# MCU_ESP32_S3.net
KiCad netlist of a schematic drawn in Altium Designer
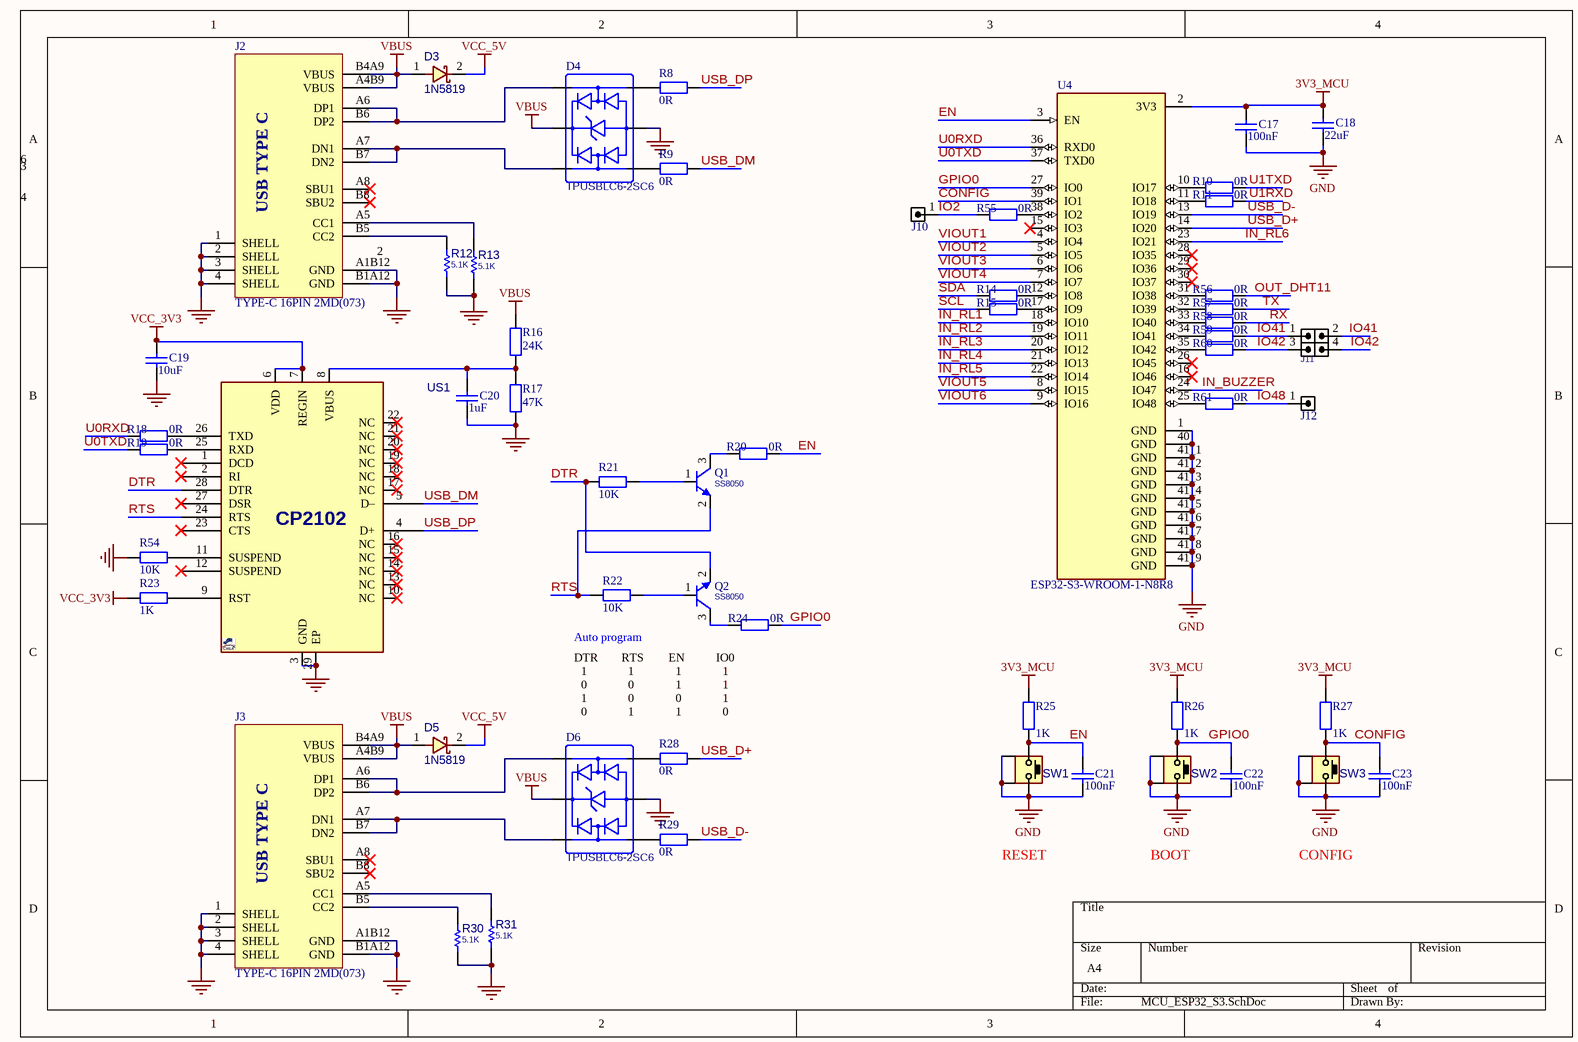
[diagram p0: MCU_ESP32_S3.SchDoc]

(export (version "E")
  (design (tool "Eeschema 10.0.6"))
  (components
    (comp (ref "C17")
      (value "100nF_0603_1%")
      (footprint "tu 0603")
      (description "Capacitor, Ceramic, 50V")
      (fields (field (name "MA_HANG") "100nF"))
      (libsource (lib "THU VIEN SCH") (part "Tu 0603 470pF 50V 10%"))
    )
    (comp (ref "C18")
      (value "22uF_0603_1%")
      (footprint "tu 0603")
      (description "Capacitor, Ceramic, 50V")
      (fields (field (name "MA_HANG") "22uF"))
      (libsource (lib "THU VIEN SCH") (part "Tu 0603 470pF 50V 10%"))
    )
    (comp (ref "C19")
      (value "10uF_0603_1%")
      (footprint "tu 0603")
      (description "Capacitor, Ceramic, 50V")
      (fields (field (name "MA_HANG") "10uF"))
      (libsource (lib "THU VIEN SCH") (part "Tu 0603 470pF 50V 10%"))
    )
    (comp (ref "C20")
      (value "1uF_0603_1%")
      (footprint "tu 0603")
      (description "Capacitor, Ceramic, 50V")
      (fields (field (name "MA_HANG") "1uF"))
      (libsource (lib "THU VIEN SCH") (part "Tu 0603 470pF 50V 10%"))
    )
    (comp (ref "C21")
      (value "100nF_0603_1%")
      (footprint "tu 0603")
      (description "Capacitor, Ceramic, 50V")
      (fields (field (name "MA_HANG") "100nF"))
      (libsource (lib "THU VIEN SCH") (part "Tu 0603 470pF 50V 10%"))
    )
    (comp (ref "C22")
      (value "100nF_0603_1%")
      (footprint "tu 0603")
      (description "Capacitor, Ceramic, 50V")
      (fields (field (name "MA_HANG") "100nF"))
      (libsource (lib "THU VIEN SCH") (part "Tu 0603 470pF 50V 10%"))
    )
    (comp (ref "C23")
      (value "100nF_0603_1%")
      (footprint "tu 0603")
      (description "Capacitor, Ceramic, 50V")
      (fields (field (name "MA_HANG") "100nF"))
      (libsource (lib "THU VIEN SCH") (part "Tu 0603 470pF 50V 10%"))
    )
    (comp (ref "D3")
      (value "1N5819")
      (footprint "D_SOD123W")
      (description "DIODE, SCHOTTKY, 40V, 1A")
      (fields (field (name "MANF") "DIODES") (field (name "MANF_P#") "1N5819HW-7-F"))
      (libsource (lib "AH_Library") (part "DIODE_SMD_SCHOTTKY_1N5819"))
    )
    (comp (ref "D4")
      (value "TPUSBLC6-2SC6")
      (footprint "SOT-23-6_L2.9-W1.6-P0.95-LS2.8-BR")
      (description "ESD ROHS SOT23-6 DIODES")
      (fields (field (name "LCSC PART NUMBER") "C558442") (field (name "MANUFACTURER") "TECH PUBLIC"))
      (libsource (lib "ESP32 S3 Gateway") (part "ESD_TPUSBLC6-2SC6"))
    )
    (comp (ref "D5")
      (value "1N5819")
      (footprint "D_SOD123W")
      (description "DIODE, SCHOTTKY, 40V, 1A")
      (fields (field (name "MANF") "DIODES") (field (name "MANF_P#") "1N5819HW-7-F"))
      (libsource (lib "AH_Library") (part "DIODE_SMD_SCHOTTKY_1N5819"))
    )
    (comp (ref "D6")
      (value "TPUSBLC6-2SC6")
      (footprint "SOT-23-6_L2.9-W1.6-P0.95-LS2.8-BR")
      (description "ESD ROHS SOT23-6 DIODES")
      (fields (field (name "LCSC PART NUMBER") "C558442") (field (name "MANUFACTURER") "TECH PUBLIC"))
      (libsource (lib "ESP32 S3 Gateway") (part "ESD_TPUSBLC6-2SC6"))
    )
    (comp (ref "J2")
      (value "TYPE-C 16PIN 2MD(073)")
      (footprint "USB-C-SMD_TYPE-C16PIN")
      (description "5A 1 Surface Mount 16 Female -25℃~+85℃ Type-C SMD USB Connectors ROHS")
      (fields
        (field (name "MANUFACTURER") "SHOU HAN")
        (field (name "MANUFACTURER PART NUMBER") "TYPE-C16PIN")
      )
      (libsource (lib "ESP32 S3 Gateway") (part "TYPE-C 16PIN 2MD(073)"))
    )
    (comp (ref "J3")
      (value "TYPE-C 16PIN 2MD(073)")
      (footprint "USB-C-SMD_TYPE-C16PIN")
      (description "5A 1 Surface Mount 16 Female -25℃~+85℃ Type-C SMD USB Connectors ROHS")
      (fields
        (field (name "MANUFACTURER") "SHOU HAN")
        (field (name "MANUFACTURER PART NUMBER") "TYPE-C16PIN")
      )
      (libsource (lib "ESP32 S3 Gateway") (part "TYPE-C 16PIN 2MD(073)"))
    )
    (comp (ref "J10")
      (value "HDRM1")
      (footprint "HDR_M_1")
      (description "CONN, HEADER, Male, pitch: 2.54mm, 1POS")
      (libsource (lib "AH_Library") (part "HDR_M_1"))
    )
    (comp (ref "J11")
      (value "HDR2M_2X2")
      (footprint "HDR2_M_2X2")
      (description "CONN, HEADER, Male, pitch: 2mm, 4POS")
      (fields (field (name "MANF_P#") "MANF_PART#") (field (name "MANF") "MANF"))
      (libsource (lib "AH_Library") (part "HDR2_M_2X2"))
    )
    (comp (ref "J12")
      (value "HDRM1")
      (footprint "HDR_M_1")
      (description "CONN, HEADER, Male, pitch: 2.54mm, 1POS")
      (libsource (lib "") (part "HDR_M_1_1"))
    )
    (comp (ref "Q1")
      (value "SS8050")
      (footprint "SOT23_3")
      (description "BJT, NPN, 25v, 1.5A, SMD, SOT23")
      (fields (field (name "MANF_P#") "MMBT8050") (field (name "MANF") "GALAXY"))
      (libsource (lib "AH_Library") (part "NPN_MMBT8050_SOT23"))
    )
    (comp (ref "Q2")
      (value "SS8050")
      (footprint "SOT23_3")
      (description "BJT, NPN, 25v, 1.5A, SMD, SOT23")
      (fields (field (name "MANF_P#") "MMBT8050") (field (name "MANF") "GALAXY"))
      (libsource (lib "AH_Library") (part "NPN_MMBT8050_SOT23"))
    )
    (comp (ref "R8")
      (value "0R_0603_1%")
      (footprint "tro smd 0603")
      (description "RES SMD 0603")
      (fields (field (name "MA_HANG") "0R"))
      (libsource (lib "THU VIEN SCH") (part "Tro 0603 5% 10k"))
    )
    (comp (ref "R9")
      (value "0R_0603_1%")
      (footprint "tro smd 0603")
      (description "RES SMD 0603")
      (fields (field (name "MA_HANG") "0R"))
      (libsource (lib "THU VIEN SCH") (part "Tro 0603 5% 10k"))
    )
    (comp (ref "R10")
      (value "0R_0603_1%")
      (footprint "tro smd 0603")
      (description "RES SMD 0603")
      (fields (field (name "MA_HANG") "0R"))
      (libsource (lib "THU VIEN SCH") (part "Tro 0603 5% 10k"))
    )
    (comp (ref "R11")
      (value "0R_0603_1%")
      (footprint "tro smd 0603")
      (description "RES SMD 0603")
      (fields (field (name "MA_HANG") "0R"))
      (libsource (lib "THU VIEN SCH") (part "Tro 0603 5% 10k"))
    )
    (comp (ref "R12")
      (value "5.1K")
      (footprint "R0603")
      (description "RESISTOR, SMD")
      (fields (field (name "Comment") "5K1_0603_1%"))
      (libsource (lib "AH_Library") (part "RES_SMD_0603"))
    )
    (comp (ref "R13")
      (value "5.1K")
      (footprint "R0603")
      (description "RESISTOR, SMD")
      (fields (field (name "Comment") "5K1_0603_1%"))
      (libsource (lib "AH_Library") (part "RES_SMD_0603"))
    )
    (comp (ref "R14")
      (value "0R_0603_1%")
      (footprint "tro smd 0603")
      (description "RES SMD 0603")
      (fields (field (name "MA_HANG") "0R"))
      (libsource (lib "THU VIEN SCH") (part "Tro 0603 5% 10k"))
    )
    (comp (ref "R15")
      (value "0R_0603_1%")
      (footprint "tro smd 0603")
      (description "RES SMD 0603")
      (fields (field (name "MA_HANG") "0R"))
      (libsource (lib "THU VIEN SCH") (part "Tro 0603 5% 10k"))
    )
    (comp (ref "R16")
      (value "24K_0603_1%")
      (footprint "tro smd 0603")
      (description "RES SMD 0603")
      (fields (field (name "MA_HANG") "24K"))
      (libsource (lib "THU VIEN SCH") (part "Tro 0603 5% 10k"))
    )
    (comp (ref "R17")
      (value "47K_0603_1%")
      (footprint "tro smd 0603")
      (description "RES SMD 0603")
      (fields (field (name "MA_HANG") "47K"))
      (libsource (lib "THU VIEN SCH") (part "Tro 0603 5% 10k"))
    )
    (comp (ref "R18")
      (value "0R_0603_1%")
      (footprint "tro smd 0603")
      (description "RES SMD 0603")
      (fields (field (name "MA_HANG") "0R"))
      (libsource (lib "THU VIEN SCH") (part "Tro 0603 5% 10k"))
    )
    (comp (ref "R19")
      (value "0R_0603_1%")
      (footprint "tro smd 0603")
      (description "RES SMD 0603")
      (fields (field (name "MA_HANG") "0R"))
      (libsource (lib "THU VIEN SCH") (part "Tro 0603 5% 10k"))
    )
    (comp (ref "R20")
      (value "0R_0603_1%")
      (footprint "tro smd 0603")
      (description "RES SMD 0603")
      (fields (field (name "MA_HANG") "0R"))
      (libsource (lib "THU VIEN SCH") (part "Tro 0603 5% 10k"))
    )
    (comp (ref "R21")
      (value "10K_0603_1%")
      (footprint "tro smd 0603")
      (description "RES SMD 0603")
      (fields (field (name "MA_HANG") "10K"))
      (libsource (lib "THU VIEN SCH") (part "Tro 0603 5% 10k"))
    )
    (comp (ref "R22")
      (value "10K_0603_1%")
      (footprint "tro smd 0603")
      (description "RES SMD 0603")
      (fields (field (name "MA_HANG") "10K"))
      (libsource (lib "THU VIEN SCH") (part "Tro 0603 5% 10k"))
    )
    (comp (ref "R23")
      (value "1K_0603_1%")
      (footprint "tro smd 0603")
      (description "RES SMD 0603")
      (fields (field (name "MA_HANG") "1K"))
      (libsource (lib "THU VIEN SCH") (part "Tro 0603 5% 10k"))
    )
    (comp (ref "R24")
      (value "0R_0603_1%")
      (footprint "tro smd 0603")
      (description "RES SMD 0603")
      (fields (field (name "MA_HANG") "0R"))
      (libsource (lib "THU VIEN SCH") (part "Tro 0603 5% 10k"))
    )
    (comp (ref "R25")
      (value "1K_0603_1%")
      (footprint "tro smd 0603")
      (description "RES SMD 0603")
      (fields (field (name "MA_HANG") "1K"))
      (libsource (lib "THU VIEN SCH") (part "Tro 0603 5% 10k"))
    )
    (comp (ref "R26")
      (value "1K_0603_1%")
      (footprint "tro smd 0603")
      (description "RES SMD 0603")
      (fields (field (name "MA_HANG") "1K"))
      (libsource (lib "THU VIEN SCH") (part "Tro 0603 5% 10k"))
    )
    (comp (ref "R27")
      (value "1K_0603_1%")
      (footprint "tro smd 0603")
      (description "RES SMD 0603")
      (fields (field (name "MA_HANG") "1K"))
      (libsource (lib "THU VIEN SCH") (part "Tro 0603 5% 10k"))
    )
    (comp (ref "R28")
      (value "0R_0603_1%")
      (footprint "tro smd 0603")
      (description "RES SMD 0603")
      (fields (field (name "MA_HANG") "0R"))
      (libsource (lib "THU VIEN SCH") (part "Tro 0603 5% 10k"))
    )
    (comp (ref "R29")
      (value "0R_0603_1%")
      (footprint "tro smd 0603")
      (description "RES SMD 0603")
      (fields (field (name "MA_HANG") "0R"))
      (libsource (lib "THU VIEN SCH") (part "Tro 0603 5% 10k"))
    )
    (comp (ref "R30")
      (value "5.1K")
      (footprint "R0603")
      (description "RESISTOR, SMD")
      (fields (field (name "Comment") "5K1_0603_1%"))
      (libsource (lib "AH_Library") (part "RES_SMD_0603"))
    )
    (comp (ref "R31")
      (value "5.1K")
      (footprint "R0603")
      (description "RESISTOR, SMD")
      (fields (field (name "Comment") "5K1_0603_1%"))
      (libsource (lib "AH_Library") (part "RES_SMD_0603"))
    )
    (comp (ref "R54")
      (value "10K_0603_1%")
      (footprint "tro smd 0603")
      (description "RES SMD 0603")
      (fields (field (name "MA_HANG") "10K"))
      (libsource (lib "THU VIEN SCH") (part "Tro 0603 5% 10k"))
    )
    (comp (ref "R55")
      (value "0R_0603_1%")
      (footprint "tro smd 0603")
      (description "RES SMD 0603")
      (fields (field (name "MA_HANG") "0R"))
      (libsource (lib "THU VIEN SCH") (part "Tro 0603 5% 10k"))
    )
    (comp (ref "R56")
      (value "0R_0603_1%")
      (footprint "tro smd 0603")
      (description "RES SMD 0603")
      (fields (field (name "MA_HANG") "0R"))
      (libsource (lib "THU VIEN SCH") (part "Tro 0603 5% 10k"))
    )
    (comp (ref "R57")
      (value "0R_0603_1%")
      (footprint "tro smd 0603")
      (description "RES SMD 0603")
      (fields (field (name "MA_HANG") "0R"))
      (libsource (lib "THU VIEN SCH") (part "Tro 0603 5% 10k"))
    )
    (comp (ref "R58")
      (value "0R_0603_1%")
      (footprint "tro smd 0603")
      (description "RES SMD 0603")
      (fields (field (name "MA_HANG") "0R"))
      (libsource (lib "THU VIEN SCH") (part "Tro 0603 5% 10k"))
    )
    (comp (ref "R59")
      (value "0R_0603_1%")
      (footprint "tro smd 0603")
      (description "RES SMD 0603")
      (fields (field (name "MA_HANG") "0R"))
      (libsource (lib "THU VIEN SCH") (part "Tro 0603 5% 10k"))
    )
    (comp (ref "R60")
      (value "0R_0603_1%")
      (footprint "tro smd 0603")
      (description "RES SMD 0603")
      (fields (field (name "MA_HANG") "0R"))
      (libsource (lib "THU VIEN SCH") (part "Tro 0603 5% 10k"))
    )
    (comp (ref "R61")
      (value "0R_0603_1%")
      (footprint "tro smd 0603")
      (description "RES SMD 0603")
      (fields (field (name "MA_HANG") "0R"))
      (libsource (lib "THU VIEN SCH") (part "Tro 0603 5% 10k"))
    )
    (comp (ref "SW1")
      (value "PUSHBUTTON")
      (footprint "SWPBT_SPST_R_6X6X10")
      (description "SWITCH, PUSH BUTTON, TACTILE, THD, SPST, RIGHT")
      (libsource (lib "AH_Library") (part "SWPBT_SPST_R_6X6X10"))
    )
    (comp (ref "SW2")
      (value "PUSHBUTTON")
      (footprint "SWPBT_SPST_R_6X6X10")
      (description "SWITCH, PUSH BUTTON, TACTILE, THD, SPST, RIGHT")
      (libsource (lib "AH_Library") (part "SWPBT_SPST_R_6X6X10"))
    )
    (comp (ref "SW3")
      (value "PUSHBUTTON")
      (footprint "SWPBT_SPST_R_6X6X10")
      (description "SWITCH, PUSH BUTTON, TACTILE, THD, SPST, RIGHT")
      (libsource (lib "AH_Library") (part "SWPBT_SPST_R_6X6X10"))
    )
    (comp (ref "U4")
      (value "ESP32-S3-WROOM-1-N8R8")
      (footprint "XCVR_ESP32S3WROOM1N8R8")
      (description "Bluetooth, WiFi 802.11b/g/n, Bluetooth v5.0 Transceiver Module 2.4GHz PCB Trace Surface Mount")
      (fields (field (name "MF") "Espressif Systems"))
      (libsource (lib "ESP32-S3-WROOM-1-N8R8") (part "ESP32-S3-WROOM-1-N8R8"))
    )
    (comp (ref "US1")
      (value "CP2102_QFN28")
      (footprint "QFN50_28T")
      (description "USB-UART BRIDGE")
      (fields (field (name "MANF") "SILICON LABS") (field (name "MANF_1") "MANF"))
      (libsource (lib "AH_Library") (part "CP2102_QFN28"))
    )
  )
  (nets
    (net (code "1") (name "/CONFIG") (class "Default")
      (node (ref "C23") (pin "1") (pinfunction "1_1") (pintype "passive"))
      (node (ref "R27") (pin "1") (pinfunction "1_1") (pintype "passive"))
      (node (ref "SW3") (pin "1") (pinfunction "1_1") (pintype "passive"))
      (node (ref "U4") (pin "39") (pinfunction "IO1_39") (pintype "bidirectional"))
    )
    (net (code "2") (name "/DTR") (class "Default")
      (node (ref "Q2") (pin "2") (pinfunction "E_2") (pintype "passive"))
      (node (ref "R21") (pin "2") (pinfunction "2_2") (pintype "passive"))
      (node (ref "US1") (pin "28") (pinfunction "DTR_28") (pintype "passive"))
    )
    (net (code "3") (name "/EN") (class "Default")
      (node (ref "C21") (pin "1") (pinfunction "1_1") (pintype "passive"))
      (node (ref "R20") (pin "2") (pinfunction "2_2") (pintype "passive"))
      (node (ref "R25") (pin "1") (pinfunction "1_1") (pintype "passive"))
      (node (ref "SW1") (pin "1") (pinfunction "1_1") (pintype "passive"))
      (node (ref "U4") (pin "3") (pinfunction "EN_3") (pintype "input"))
    )
    (net (code "4") (name "/GPIO0") (class "Default")
      (node (ref "C22") (pin "1") (pinfunction "1_1") (pintype "passive"))
      (node (ref "R24") (pin "2") (pinfunction "2_2") (pintype "passive"))
      (node (ref "R26") (pin "1") (pinfunction "1_1") (pintype "passive"))
      (node (ref "SW2") (pin "1") (pinfunction "1_1") (pintype "passive"))
      (node (ref "U4") (pin "27") (pinfunction "IO0_27") (pintype "bidirectional"))
    )
    (net (code "5") (name "/IN_BUZZER") (class "Default")
      (node (ref "U4") (pin "24") (pinfunction "IO47_24") (pintype "bidirectional"))
    )
    (net (code "6") (name "/IN_RL1") (class "Default")
      (node (ref "U4") (pin "18") (pinfunction "IO10_18") (pintype "bidirectional"))
    )
    (net (code "7") (name "/IN_RL2") (class "Default")
      (node (ref "U4") (pin "19") (pinfunction "IO11_19") (pintype "bidirectional"))
    )
    (net (code "8") (name "/IN_RL3") (class "Default")
      (node (ref "U4") (pin "20") (pinfunction "IO12_20") (pintype "bidirectional"))
    )
    (net (code "9") (name "/IN_RL4") (class "Default")
      (node (ref "U4") (pin "21") (pinfunction "IO13_21") (pintype "bidirectional"))
    )
    (net (code "10") (name "/IN_RL5") (class "Default")
      (node (ref "U4") (pin "22") (pinfunction "IO14_22") (pintype "bidirectional"))
    )
    (net (code "11") (name "/IN_RL6") (class "Default")
      (node (ref "U4") (pin "23") (pinfunction "IO21_23") (pintype "bidirectional"))
    )
    (net (code "12") (name "/IO2") (class "Default")
      (node (ref "J10") (pin "1") (pinfunction "1_1") (pintype "passive"))
      (node (ref "R55") (pin "1") (pinfunction "1_1") (pintype "passive"))
    )
    (net (code "13") (name "/IO41") (class "Default")
      (node (ref "J11") (pin "1") (pinfunction "1_1") (pintype "passive"))
      (node (ref "J11") (pin "2") (pinfunction "2_2") (pintype "passive"))
      (node (ref "R59") (pin "2") (pinfunction "2_2") (pintype "passive"))
    )
    (net (code "14") (name "/IO42") (class "Default")
      (node (ref "J11") (pin "3") (pinfunction "3_3") (pintype "passive"))
      (node (ref "J11") (pin "4") (pinfunction "4_4") (pintype "passive"))
      (node (ref "R60") (pin "2") (pinfunction "2_2") (pintype "passive"))
    )
    (net (code "15") (name "/IO48") (class "Default")
      (node (ref "J12") (pin "1") (pinfunction "1_1") (pintype "passive"))
      (node (ref "R61") (pin "2") (pinfunction "2_2") (pintype "passive"))
    )
    (net (code "16") (name "/OUT_DHT11") (class "Default")
      (node (ref "R56") (pin "2") (pinfunction "2_2") (pintype "passive"))
    )
    (net (code "17") (name "/RTS") (class "Default")
      (node (ref "Q1") (pin "2") (pinfunction "E_2") (pintype "passive"))
      (node (ref "R22") (pin "2") (pinfunction "2_2") (pintype "passive"))
      (node (ref "US1") (pin "24") (pinfunction "RTS_24") (pintype "passive"))
    )
    (net (code "18") (name "/RX") (class "Default")
      (node (ref "R58") (pin "2") (pinfunction "2_2") (pintype "passive"))
    )
    (net (code "19") (name "/SCL") (class "Default")
      (node (ref "R15") (pin "1") (pinfunction "1_1") (pintype "passive"))
    )
    (net (code "20") (name "/SDA") (class "Default")
      (node (ref "R14") (pin "1") (pinfunction "1_1") (pintype "passive"))
    )
    (net (code "21") (name "/TX") (class "Default")
      (node (ref "R57") (pin "2") (pinfunction "2_2") (pintype "passive"))
    )
    (net (code "22") (name "/U0RXD") (class "Default")
      (node (ref "R18") (pin "1") (pinfunction "1_1") (pintype "passive"))
      (node (ref "U4") (pin "36") (pinfunction "RXD0_36") (pintype "bidirectional"))
    )
    (net (code "23") (name "/U0TXD") (class "Default")
      (node (ref "R19") (pin "1") (pinfunction "1_1") (pintype "passive"))
      (node (ref "U4") (pin "37") (pinfunction "TXD0_37") (pintype "bidirectional"))
    )
    (net (code "24") (name "/U1RXD") (class "Default")
      (node (ref "R11") (pin "2") (pinfunction "2_2") (pintype "passive"))
    )
    (net (code "25") (name "/U1TXD") (class "Default")
      (node (ref "R10") (pin "2") (pinfunction "2_2") (pintype "passive"))
    )
    (net (code "26") (name "/USB_D+") (class "Default")
      (node (ref "R28") (pin "2") (pinfunction "2_2") (pintype "passive"))
      (node (ref "U4") (pin "14") (pinfunction "IO20_14") (pintype "bidirectional"))
    )
    (net (code "27") (name "/USB_D-") (class "Default")
      (node (ref "R29") (pin "2") (pinfunction "2_2") (pintype "passive"))
      (node (ref "U4") (pin "13") (pinfunction "IO19_13") (pintype "bidirectional"))
    )
    (net (code "28") (name "/USB_DM") (class "Default")
      (node (ref "R9") (pin "2") (pinfunction "2_2") (pintype "passive"))
      (node (ref "US1") (pin "5") (pinfunction "D–_5") (pintype "passive"))
    )
    (net (code "29") (name "/USB_DP") (class "Default")
      (node (ref "R8") (pin "2") (pinfunction "2_2") (pintype "passive"))
      (node (ref "US1") (pin "4") (pinfunction "D+_4") (pintype "passive"))
    )
    (net (code "30") (name "/VIOUT1") (class "Default")
      (node (ref "U4") (pin "4") (pinfunction "IO4_4") (pintype "bidirectional"))
    )
    (net (code "31") (name "/VIOUT2") (class "Default")
      (node (ref "U4") (pin "5") (pinfunction "IO5_5") (pintype "bidirectional"))
    )
    (net (code "32") (name "/VIOUT3") (class "Default")
      (node (ref "U4") (pin "6") (pinfunction "IO6_6") (pintype "bidirectional"))
    )
    (net (code "33") (name "/VIOUT4") (class "Default")
      (node (ref "U4") (pin "7") (pinfunction "IO7_7") (pintype "bidirectional"))
    )
    (net (code "34") (name "/VIOUT5") (class "Default")
      (node (ref "U4") (pin "8") (pinfunction "IO15_8") (pintype "bidirectional"))
    )
    (net (code "35") (name "/VIOUT6") (class "Default")
      (node (ref "U4") (pin "9") (pinfunction "IO16_9") (pintype "bidirectional"))
    )
    (net (code "36") (name "3V3_MCU") (class "Default")
      (node (ref "C17") (pin "1") (pinfunction "1_1") (pintype "passive"))
      (node (ref "C18") (pin "1") (pinfunction "1_1") (pintype "passive"))
      (node (ref "R25") (pin "2") (pinfunction "2_2") (pintype "passive"))
      (node (ref "R26") (pin "2") (pinfunction "2_2") (pintype "passive"))
      (node (ref "R27") (pin "2") (pinfunction "2_2") (pintype "passive"))
      (node (ref "U4") (pin "2") (pinfunction "3V3_2") (pintype "power_in"))
    )
    (net (code "37") (name "GND") (class "Default")
      (node (ref "C17") (pin "2") (pinfunction "2_2") (pintype "passive"))
      (node (ref "C18") (pin "2") (pinfunction "2_2") (pintype "passive"))
      (node (ref "C19") (pin "2") (pinfunction "2_2") (pintype "passive"))
      (node (ref "C20") (pin "2") (pinfunction "2_2") (pintype "passive"))
      (node (ref "C21") (pin "2") (pinfunction "2_2") (pintype "passive"))
      (node (ref "C22") (pin "2") (pinfunction "2_2") (pintype "passive"))
      (node (ref "C23") (pin "2") (pinfunction "2_2") (pintype "passive"))
      (node (ref "D4") (pin "2") (pinfunction "GND_2") (pintype "passive"))
      (node (ref "D6") (pin "2") (pinfunction "GND_2") (pintype "passive"))
      (node (ref "J2") (pin "1") (pinfunction "SHELL_1") (pintype "passive"))
      (node (ref "J2") (pin "2") (pinfunction "SHELL_2") (pintype "passive"))
      (node (ref "J2") (pin "3") (pinfunction "SHELL_3") (pintype "passive"))
      (node (ref "J2") (pin "4") (pinfunction "SHELL_4") (pintype "passive"))
      (node (ref "J2") (pin "A1B12") (pinfunction "GND_A1B12") (pintype "passive"))
      (node (ref "J2") (pin "B1A12") (pinfunction "GND_B1A12") (pintype "passive"))
      (node (ref "J3") (pin "1") (pinfunction "SHELL_1") (pintype "passive"))
      (node (ref "J3") (pin "2") (pinfunction "SHELL_2") (pintype "passive"))
      (node (ref "J3") (pin "3") (pinfunction "SHELL_3") (pintype "passive"))
      (node (ref "J3") (pin "4") (pinfunction "SHELL_4") (pintype "passive"))
      (node (ref "J3") (pin "A1B12") (pinfunction "GND_A1B12") (pintype "passive"))
      (node (ref "J3") (pin "B1A12") (pinfunction "GND_B1A12") (pintype "passive"))
      (node (ref "R12") (pin "2") (pinfunction "2_2") (pintype "passive"))
      (node (ref "R13") (pin "2") (pinfunction "2_2") (pintype "passive"))
      (node (ref "R17") (pin "2") (pinfunction "2_2") (pintype "passive"))
      (node (ref "R30") (pin "2") (pinfunction "2_2") (pintype "passive"))
      (node (ref "R31") (pin "2") (pinfunction "2_2") (pintype "passive"))
      (node (ref "R54") (pin "2") (pinfunction "2_2") (pintype "passive"))
      (node (ref "SW1") (pin "2") (pinfunction "2_2") (pintype "passive"))
      (node (ref "SW1") (pin "MH1") (pinfunction "MH1_MH1") (pintype "passive"))
      (node (ref "SW1") (pin "MH2") (pinfunction "MH2_MH2") (pintype "passive"))
      (node (ref "SW2") (pin "2") (pinfunction "2_2") (pintype "passive"))
      (node (ref "SW2") (pin "MH1") (pinfunction "MH1_MH1") (pintype "passive"))
      (node (ref "SW2") (pin "MH2") (pinfunction "MH2_MH2") (pintype "passive"))
      (node (ref "SW3") (pin "2") (pinfunction "2_2") (pintype "passive"))
      (node (ref "SW3") (pin "MH1") (pinfunction "MH1_MH1") (pintype "passive"))
      (node (ref "SW3") (pin "MH2") (pinfunction "MH2_MH2") (pintype "passive"))
      (node (ref "U4") (pin "1") (pinfunction "GND_1") (pintype "power_in"))
      (node (ref "U4") (pin "40") (pinfunction "GND_40") (pintype "power_in"))
      (node (ref "U4") (pin "41_1") (pinfunction "GND_41_1") (pintype "power_in"))
      (node (ref "U4") (pin "41_2") (pinfunction "GND_41_2") (pintype "power_in"))
      (node (ref "U4") (pin "41_3") (pinfunction "GND_41_3") (pintype "power_in"))
      (node (ref "U4") (pin "41_4") (pinfunction "GND_41_4") (pintype "power_in"))
      (node (ref "U4") (pin "41_5") (pinfunction "GND_41_5") (pintype "power_in"))
      (node (ref "U4") (pin "41_6") (pinfunction "GND_41_6") (pintype "power_in"))
      (node (ref "U4") (pin "41_7") (pinfunction "GND_41_7") (pintype "power_in"))
      (node (ref "U4") (pin "41_8") (pinfunction "GND_41_8") (pintype "power_in"))
      (node (ref "U4") (pin "41_9") (pinfunction "GND_41_9") (pintype "power_in"))
      (node (ref "US1") (pin "29") (pinfunction "EP_29") (pintype "passive"))
      (node (ref "US1") (pin "3") (pinfunction "GND_3") (pintype "passive"))
    )
    (net (code "38") (name "Net-(D4-I{slash}O1-Pad1)") (class "Default")
      (node (ref "D4") (pin "1") (pinfunction "I/O1_1") (pintype "passive"))
      (node (ref "R8") (pin "1") (pinfunction "1_1") (pintype "passive"))
    )
    (net (code "39") (name "Net-(D4-I{slash}O2-Pad3)") (class "Default")
      (node (ref "D4") (pin "3") (pinfunction "I/O2_3") (pintype "passive"))
      (node (ref "R9") (pin "1") (pinfunction "1_1") (pintype "passive"))
    )
    (net (code "40") (name "Net-(D6-I{slash}O1-Pad1)") (class "Default")
      (node (ref "D6") (pin "1") (pinfunction "I/O1_1") (pintype "passive"))
      (node (ref "R28") (pin "1") (pinfunction "1_1") (pintype "passive"))
    )
    (net (code "41") (name "Net-(D6-I{slash}O2-Pad3)") (class "Default")
      (node (ref "D6") (pin "3") (pinfunction "I/O2_3") (pintype "passive"))
      (node (ref "R29") (pin "1") (pinfunction "1_1") (pintype "passive"))
    )
    (net (code "42") (name "Net-(J2-CC1)") (class "Default")
      (node (ref "J2") (pin "A5") (pinfunction "CC1_A5") (pintype "passive"))
      (node (ref "R13") (pin "1") (pinfunction "1_1") (pintype "passive"))
    )
    (net (code "43") (name "Net-(J2-CC2)") (class "Default")
      (node (ref "J2") (pin "B5") (pinfunction "CC2_B5") (pintype "passive"))
      (node (ref "R12") (pin "1") (pinfunction "1_1") (pintype "passive"))
    )
    (net (code "44") (name "Net-(J2-DN1)") (class "Default")
      (node (ref "D4") (pin "4") (pinfunction "I/O2_4") (pintype "passive"))
      (node (ref "J2") (pin "A7") (pinfunction "DN1_A7") (pintype "passive"))
      (node (ref "J2") (pin "B7") (pinfunction "DN2_B7") (pintype "passive"))
    )
    (net (code "45") (name "Net-(J2-DP1)") (class "Default")
      (node (ref "D4") (pin "6") (pinfunction "I/O1_6") (pintype "passive"))
      (node (ref "J2") (pin "A6") (pinfunction "DP1_A6") (pintype "passive"))
      (node (ref "J2") (pin "B6") (pinfunction "DP2_B6") (pintype "passive"))
    )
    (net (code "46") (name "Net-(J3-CC1)") (class "Default")
      (node (ref "J3") (pin "A5") (pinfunction "CC1_A5") (pintype "passive"))
      (node (ref "R31") (pin "1") (pinfunction "1_1") (pintype "passive"))
    )
    (net (code "47") (name "Net-(J3-CC2)") (class "Default")
      (node (ref "J3") (pin "B5") (pinfunction "CC2_B5") (pintype "passive"))
      (node (ref "R30") (pin "1") (pinfunction "1_1") (pintype "passive"))
    )
    (net (code "48") (name "Net-(J3-DN1)") (class "Default")
      (node (ref "D6") (pin "4") (pinfunction "I/O2_4") (pintype "passive"))
      (node (ref "J3") (pin "A7") (pinfunction "DN1_A7") (pintype "passive"))
      (node (ref "J3") (pin "B7") (pinfunction "DN2_B7") (pintype "passive"))
    )
    (net (code "49") (name "Net-(J3-DP1)") (class "Default")
      (node (ref "D6") (pin "6") (pinfunction "I/O1_6") (pintype "passive"))
      (node (ref "J3") (pin "A6") (pinfunction "DP1_A6") (pintype "passive"))
      (node (ref "J3") (pin "B6") (pinfunction "DP2_B6") (pintype "passive"))
    )
    (net (code "50") (name "Net-(Q1-B)") (class "Default")
      (node (ref "Q1") (pin "1") (pinfunction "B_1") (pintype "passive"))
      (node (ref "R21") (pin "1") (pinfunction "1_1") (pintype "passive"))
    )
    (net (code "51") (name "Net-(Q1-C)") (class "Default")
      (node (ref "Q1") (pin "3") (pinfunction "C_3") (pintype "passive"))
      (node (ref "R20") (pin "1") (pinfunction "1_1") (pintype "passive"))
    )
    (net (code "52") (name "Net-(Q2-B)") (class "Default")
      (node (ref "Q2") (pin "1") (pinfunction "B_1") (pintype "passive"))
      (node (ref "R22") (pin "1") (pinfunction "1_1") (pintype "passive"))
    )
    (net (code "53") (name "Net-(Q2-C)") (class "Default")
      (node (ref "Q2") (pin "3") (pinfunction "C_3") (pintype "passive"))
      (node (ref "R24") (pin "1") (pinfunction "1_1") (pintype "passive"))
    )
    (net (code "54") (name "Net-(R54-Pad1)") (class "Default")
      (node (ref "R54") (pin "1") (pinfunction "1_1") (pintype "passive"))
      (node (ref "US1") (pin "11") (pinfunction "SUSPEND_11") (pintype "passive"))
    )
    (net (code "55") (name "Net-(U4-IO2)") (class "Default")
      (node (ref "R55") (pin "2") (pinfunction "2_2") (pintype "passive"))
      (node (ref "U4") (pin "38") (pinfunction "IO2_38") (pintype "bidirectional"))
    )
    (net (code "56") (name "Net-(U4-IO8)") (class "Default")
      (node (ref "R14") (pin "2") (pinfunction "2_2") (pintype "passive"))
      (node (ref "U4") (pin "12") (pinfunction "IO8_12") (pintype "bidirectional"))
    )
    (net (code "57") (name "Net-(U4-IO9)") (class "Default")
      (node (ref "R15") (pin "2") (pinfunction "2_2") (pintype "passive"))
      (node (ref "U4") (pin "17") (pinfunction "IO9_17") (pintype "bidirectional"))
    )
    (net (code "58") (name "Net-(U4-IO17)") (class "Default")
      (node (ref "R10") (pin "1") (pinfunction "1_1") (pintype "passive"))
      (node (ref "U4") (pin "10") (pinfunction "IO17_10") (pintype "bidirectional"))
    )
    (net (code "59") (name "Net-(U4-IO18)") (class "Default")
      (node (ref "R11") (pin "1") (pinfunction "1_1") (pintype "passive"))
      (node (ref "U4") (pin "11") (pinfunction "IO18_11") (pintype "bidirectional"))
    )
    (net (code "60") (name "Net-(U4-IO38)") (class "Default")
      (node (ref "R56") (pin "1") (pinfunction "1_1") (pintype "passive"))
      (node (ref "U4") (pin "31") (pinfunction "IO38_31") (pintype "bidirectional"))
    )
    (net (code "61") (name "Net-(U4-IO39)") (class "Default")
      (node (ref "R57") (pin "1") (pinfunction "1_1") (pintype "passive"))
      (node (ref "U4") (pin "32") (pinfunction "IO39_32") (pintype "bidirectional"))
    )
    (net (code "62") (name "Net-(U4-IO40)") (class "Default")
      (node (ref "R58") (pin "1") (pinfunction "1_1") (pintype "passive"))
      (node (ref "U4") (pin "33") (pinfunction "IO40_33") (pintype "bidirectional"))
    )
    (net (code "63") (name "Net-(U4-IO41)") (class "Default")
      (node (ref "R59") (pin "1") (pinfunction "1_1") (pintype "passive"))
      (node (ref "U4") (pin "34") (pinfunction "IO41_34") (pintype "bidirectional"))
    )
    (net (code "64") (name "Net-(U4-IO42)") (class "Default")
      (node (ref "R60") (pin "1") (pinfunction "1_1") (pintype "passive"))
      (node (ref "U4") (pin "35") (pinfunction "IO42_35") (pintype "bidirectional"))
    )
    (net (code "65") (name "Net-(U4-IO48)") (class "Default")
      (node (ref "R61") (pin "1") (pinfunction "1_1") (pintype "passive"))
      (node (ref "U4") (pin "25") (pinfunction "IO48_25") (pintype "bidirectional"))
    )
    (net (code "66") (name "Net-(US1-RST)") (class "Default")
      (node (ref "R23") (pin "2") (pinfunction "2_2") (pintype "passive"))
      (node (ref "US1") (pin "9") (pinfunction "RST_9") (pintype "passive"))
    )
    (net (code "67") (name "Net-(US1-RXD)") (class "Default")
      (node (ref "R19") (pin "2") (pinfunction "2_2") (pintype "passive"))
      (node (ref "US1") (pin "25") (pinfunction "RXD_25") (pintype "passive"))
    )
    (net (code "68") (name "Net-(US1-TXD)") (class "Default")
      (node (ref "R18") (pin "2") (pinfunction "2_2") (pintype "passive"))
      (node (ref "US1") (pin "26") (pinfunction "TXD_26") (pintype "passive"))
    )
    (net (code "69") (name "Net-(US1-VBUS)") (class "Default")
      (node (ref "C20") (pin "1") (pinfunction "1_1") (pintype "passive"))
      (node (ref "R16") (pin "2") (pinfunction "2_2") (pintype "passive"))
      (node (ref "R17") (pin "1") (pinfunction "1_1") (pintype "passive"))
      (node (ref "US1") (pin "8") (pinfunction "VBUS_8") (pintype "passive"))
    )
    (net (code "70") (name "VBUS") (class "Default")
      (node (ref "D3") (pin "1") (pinfunction "1_1") (pintype "passive"))
      (node (ref "D4") (pin "5") (pinfunction "VBUS_5") (pintype "passive"))
      (node (ref "D5") (pin "1") (pinfunction "1_1") (pintype "passive"))
      (node (ref "D6") (pin "5") (pinfunction "VBUS_5") (pintype "passive"))
      (node (ref "J2") (pin "A4B9") (pinfunction "VBUS_A4B9") (pintype "passive"))
      (node (ref "J2") (pin "B4A9") (pinfunction "VBUS_B4A9") (pintype "passive"))
      (node (ref "J3") (pin "A4B9") (pinfunction "VBUS_A4B9") (pintype "passive"))
      (node (ref "J3") (pin "B4A9") (pinfunction "VBUS_B4A9") (pintype "passive"))
      (node (ref "R16") (pin "1") (pinfunction "1_1") (pintype "passive"))
    )
    (net (code "71") (name "VCC_3V3") (class "Default")
      (node (ref "C19") (pin "1") (pinfunction "1_1") (pintype "passive"))
      (node (ref "R23") (pin "1") (pinfunction "1_1") (pintype "passive"))
      (node (ref "US1") (pin "6") (pinfunction "VDD_6") (pintype "passive"))
      (node (ref "US1") (pin "7") (pinfunction "REGIN_7") (pintype "passive"))
    )
    (net (code "72") (name "VCC_5V") (class "Default")
      (node (ref "D3") (pin "2") (pinfunction "2_2") (pintype "passive"))
      (node (ref "D5") (pin "2") (pinfunction "2_2") (pintype "passive"))
    )
    (net (code "73") (name "unconnected-(J2-SBU1-PadA8)") (class "Default")
      (node (ref "J2") (pin "A8") (pinfunction "SBU1_A8") (pintype "passive+no_connect"))
    )
    (net (code "74") (name "unconnected-(J2-SBU2-PadB8)") (class "Default")
      (node (ref "J2") (pin "B8") (pinfunction "SBU2_B8") (pintype "passive+no_connect"))
    )
    (net (code "75") (name "unconnected-(J3-SBU1-PadA8)") (class "Default")
      (node (ref "J3") (pin "A8") (pinfunction "SBU1_A8") (pintype "passive+no_connect"))
    )
    (net (code "76") (name "unconnected-(J3-SBU2-PadB8)") (class "Default")
      (node (ref "J3") (pin "B8") (pinfunction "SBU2_B8") (pintype "passive+no_connect"))
    )
    (net (code "77") (name "unconnected-(U4-IO3-Pad15)") (class "Default")
      (node (ref "U4") (pin "15") (pinfunction "IO3_15") (pintype "bidirectional+no_connect"))
    )
    (net (code "78") (name "unconnected-(U4-IO35-Pad28)") (class "Default")
      (node (ref "U4") (pin "28") (pinfunction "IO35_28") (pintype "bidirectional+no_connect"))
    )
    (net (code "79") (name "unconnected-(U4-IO36-Pad29)") (class "Default")
      (node (ref "U4") (pin "29") (pinfunction "IO36_29") (pintype "bidirectional+no_connect"))
    )
    (net (code "80") (name "unconnected-(U4-IO37-Pad30)") (class "Default")
      (node (ref "U4") (pin "30") (pinfunction "IO37_30") (pintype "bidirectional+no_connect"))
    )
    (net (code "81") (name "unconnected-(U4-IO45-Pad26)") (class "Default")
      (node (ref "U4") (pin "26") (pinfunction "IO45_26") (pintype "bidirectional+no_connect"))
    )
    (net (code "82") (name "unconnected-(U4-IO46-Pad16)") (class "Default")
      (node (ref "U4") (pin "16") (pinfunction "IO46_16") (pintype "bidirectional+no_connect"))
    )
    (net (code "83") (name "unconnected-(US1-CTS-Pad23)") (class "Default")
      (node (ref "US1") (pin "23") (pinfunction "CTS_23") (pintype "passive+no_connect"))
    )
    (net (code "84") (name "unconnected-(US1-DCD-Pad1)") (class "Default")
      (node (ref "US1") (pin "1") (pinfunction "DCD_1") (pintype "passive+no_connect"))
    )
    (net (code "85") (name "unconnected-(US1-DSR-Pad27)") (class "Default")
      (node (ref "US1") (pin "27") (pinfunction "DSR_27") (pintype "passive+no_connect"))
    )
    (net (code "86") (name "unconnected-(US1-NC-Pad10)") (class "Default")
      (node (ref "US1") (pin "10") (pinfunction "NC_10") (pintype "passive+no_connect"))
    )
    (net (code "87") (name "unconnected-(US1-NC-Pad13)") (class "Default")
      (node (ref "US1") (pin "13") (pinfunction "NC_13") (pintype "passive+no_connect"))
    )
    (net (code "88") (name "unconnected-(US1-NC-Pad14)") (class "Default")
      (node (ref "US1") (pin "14") (pinfunction "NC_14") (pintype "passive+no_connect"))
    )
    (net (code "89") (name "unconnected-(US1-NC-Pad15)") (class "Default")
      (node (ref "US1") (pin "15") (pinfunction "NC_15") (pintype "passive+no_connect"))
    )
    (net (code "90") (name "unconnected-(US1-NC-Pad16)") (class "Default")
      (node (ref "US1") (pin "16") (pinfunction "NC_16") (pintype "passive+no_connect"))
    )
    (net (code "91") (name "unconnected-(US1-NC-Pad17)") (class "Default")
      (node (ref "US1") (pin "17") (pinfunction "NC_17") (pintype "passive+no_connect"))
    )
    (net (code "92") (name "unconnected-(US1-NC-Pad18)") (class "Default")
      (node (ref "US1") (pin "18") (pinfunction "NC_18") (pintype "passive+no_connect"))
    )
    (net (code "93") (name "unconnected-(US1-NC-Pad19)") (class "Default")
      (node (ref "US1") (pin "19") (pinfunction "NC_19") (pintype "passive+no_connect"))
    )
    (net (code "94") (name "unconnected-(US1-NC-Pad20)") (class "Default")
      (node (ref "US1") (pin "20") (pinfunction "NC_20") (pintype "passive+no_connect"))
    )
    (net (code "95") (name "unconnected-(US1-NC-Pad21)") (class "Default")
      (node (ref "US1") (pin "21") (pinfunction "NC_21") (pintype "passive+no_connect"))
    )
    (net (code "96") (name "unconnected-(US1-NC-Pad22)") (class "Default")
      (node (ref "US1") (pin "22") (pinfunction "NC_22") (pintype "passive+no_connect"))
    )
    (net (code "97") (name "unconnected-(US1-RI-Pad2)") (class "Default")
      (node (ref "US1") (pin "2") (pinfunction "RI_2") (pintype "passive+no_connect"))
    )
    (net (code "98") (name "unconnected-(US1-SUSPEND-Pad12)") (class "Default")
      (node (ref "US1") (pin "12") (pinfunction "SUSPEND_12") (pintype "passive+no_connect"))
    )
  )
)
